# RX8Edaughter.net
KiCad netlist of a schematic drawn in EAGLE
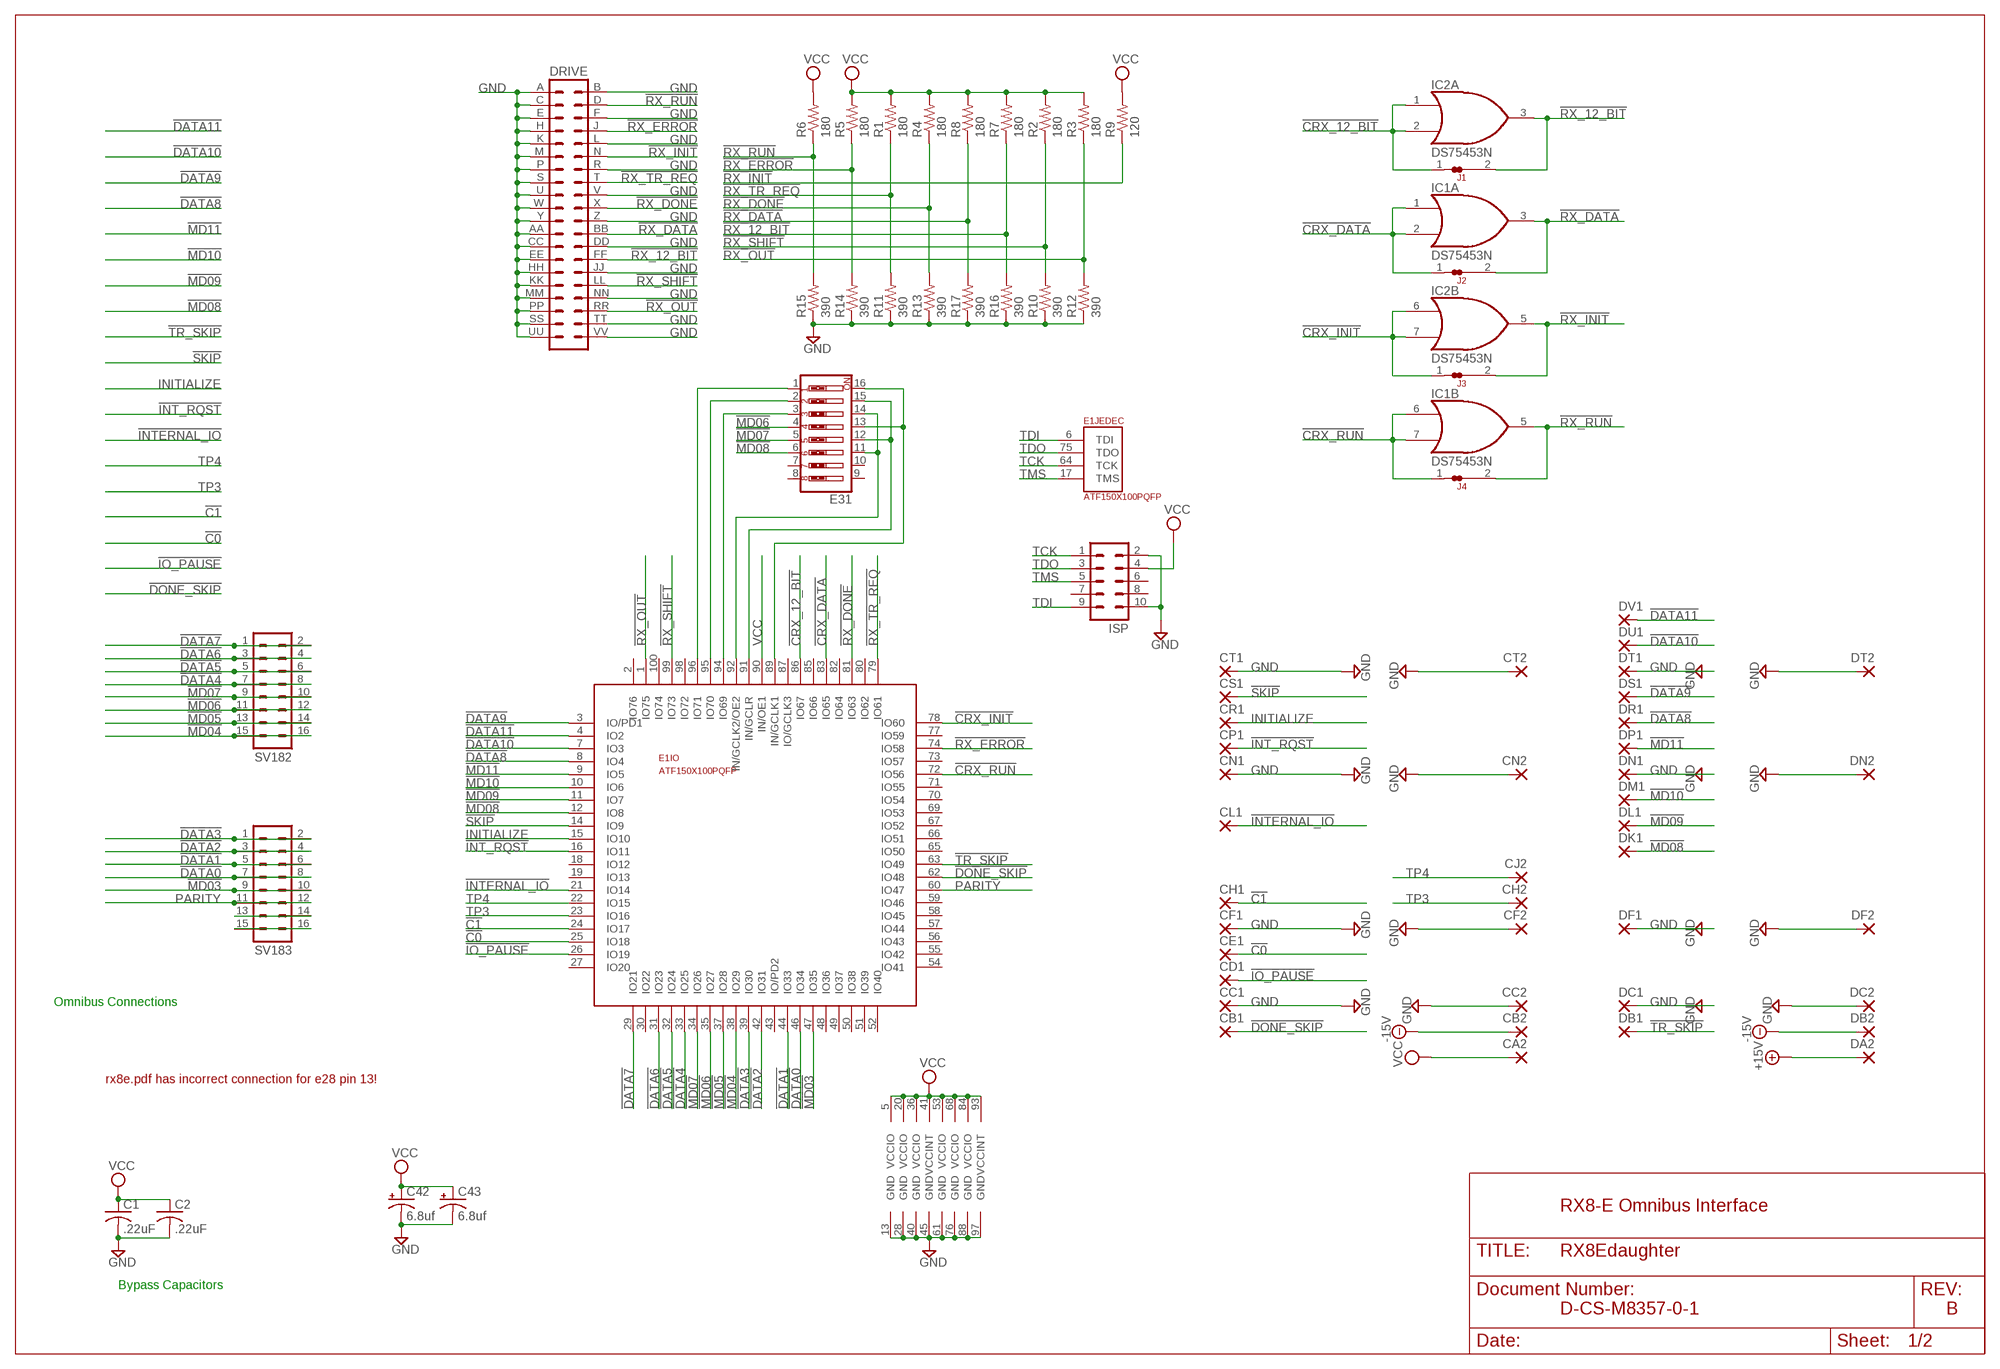
[diagram p0: schematic, sheet 1]
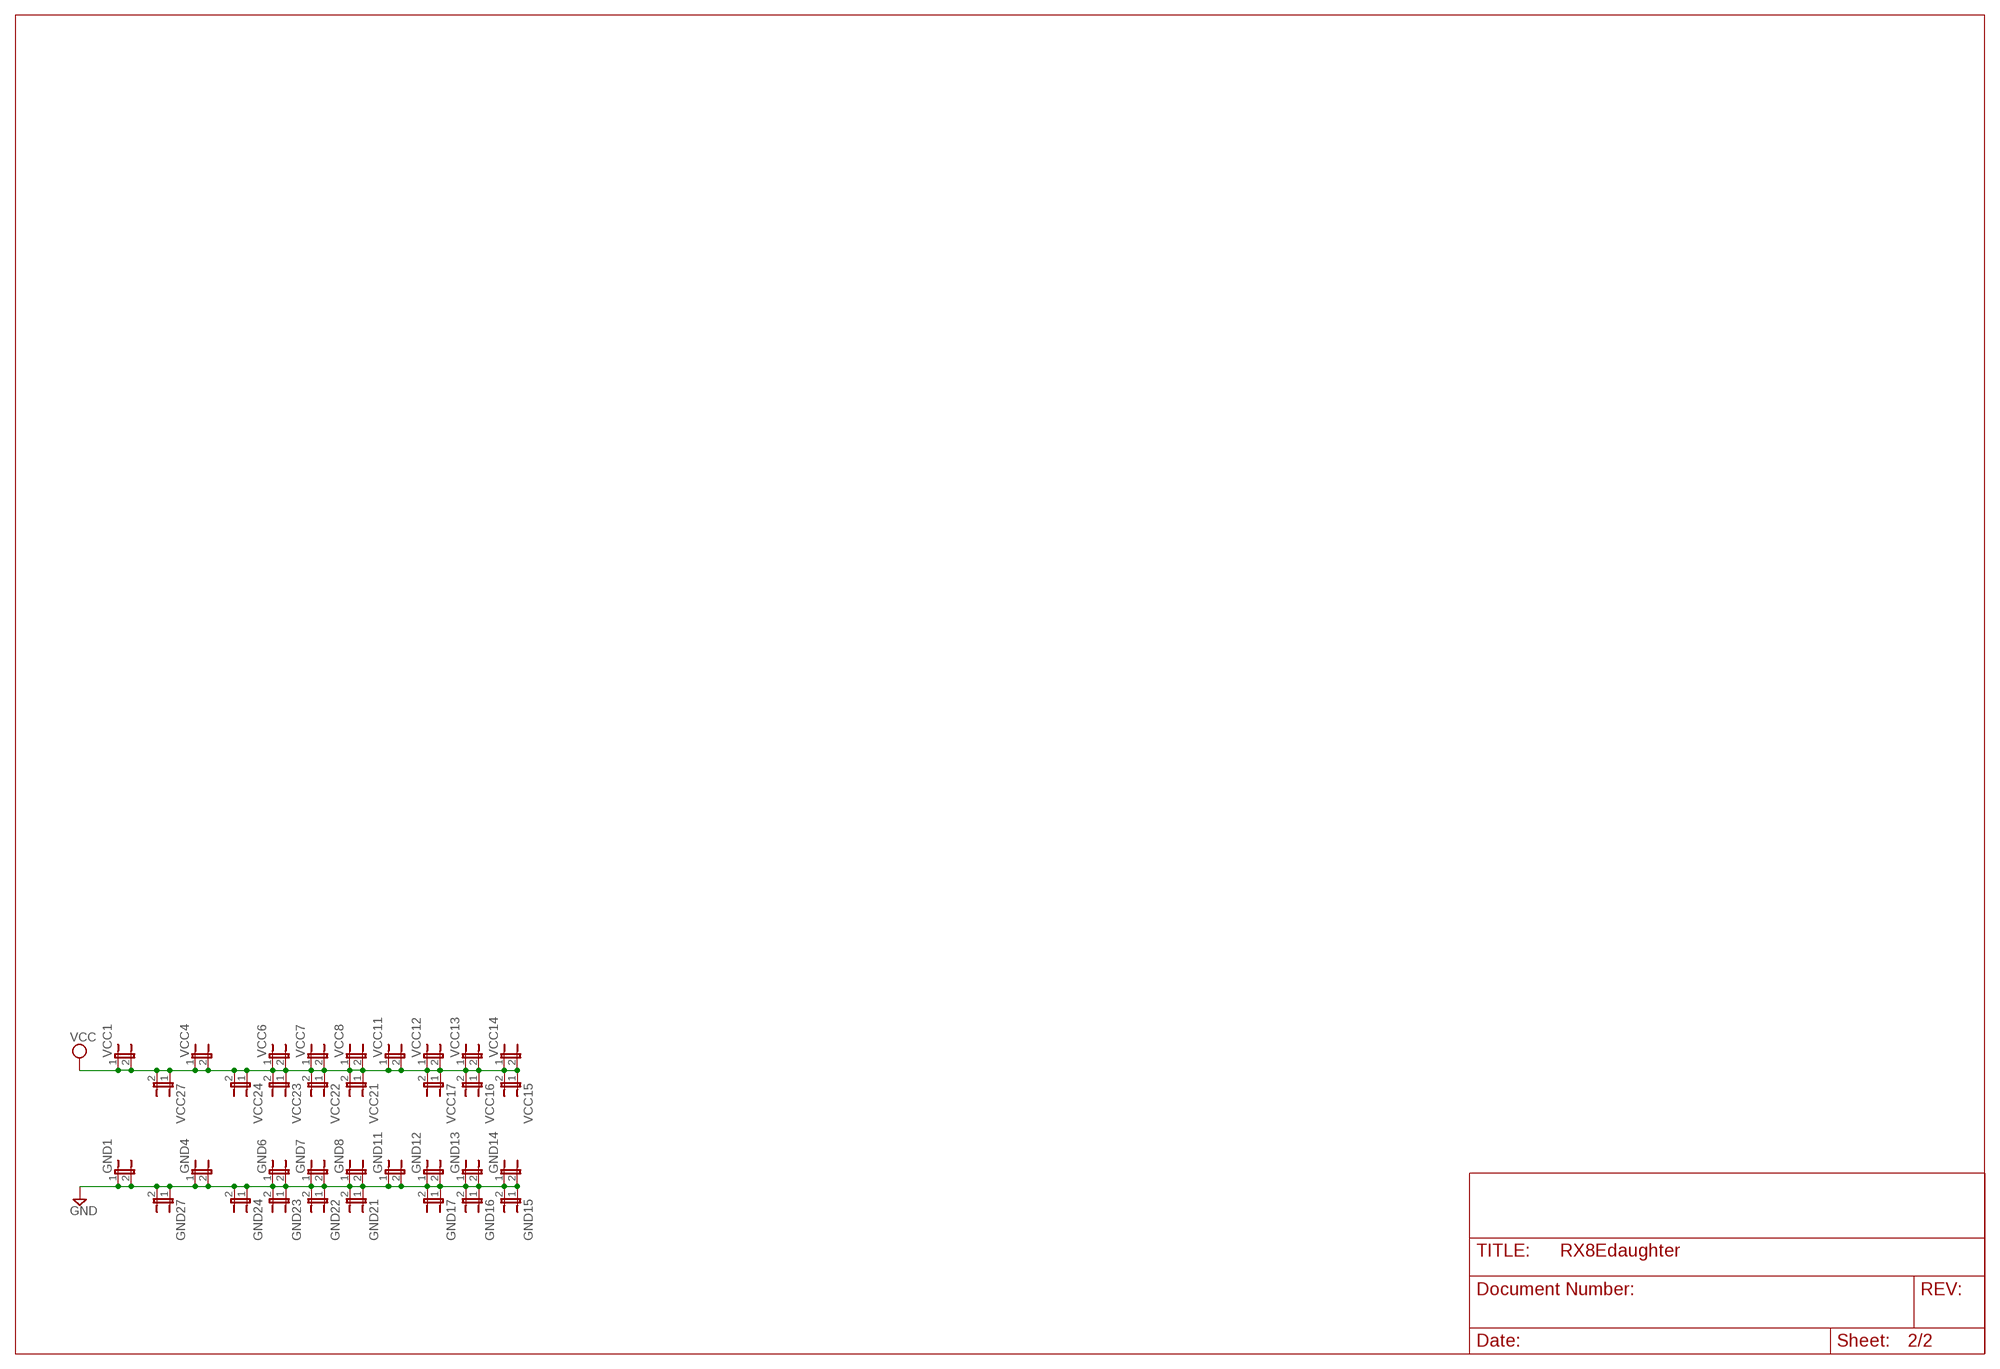
[diagram p1: schematic, sheet 2]

(export (version "E")
  (design (tool "Eeschema 10.0.6"))
  (components
    (comp (ref "GND1")
      (value "JP1E")
      (footprint "eagle-import:JP1")
      (libsource (lib "eagle-import") (part "JP1E"))
    )
    (comp (ref "GND4")
      (value "JP1E")
      (footprint "eagle-import:JP1")
      (libsource (lib "eagle-import") (part "JP1E"))
    )
    (comp (ref "GND6")
      (value "JP1E")
      (footprint "eagle-import:JP1")
      (libsource (lib "eagle-import") (part "JP1E"))
    )
    (comp (ref "GND7")
      (value "JP1E")
      (footprint "eagle-import:JP1")
      (libsource (lib "eagle-import") (part "JP1E"))
    )
    (comp (ref "GND8")
      (value "JP1E")
      (footprint "eagle-import:JP1")
      (libsource (lib "eagle-import") (part "JP1E"))
    )
    (comp (ref "GND11")
      (value "JP1E")
      (footprint "eagle-import:JP1")
      (libsource (lib "eagle-import") (part "JP1E"))
    )
    (comp (ref "GND12")
      (value "JP1E")
      (footprint "eagle-import:JP1")
      (libsource (lib "eagle-import") (part "JP1E"))
    )
    (comp (ref "GND13")
      (value "JP1E")
      (footprint "eagle-import:JP1")
      (libsource (lib "eagle-import") (part "JP1E"))
    )
    (comp (ref "GND14")
      (value "JP1E")
      (footprint "eagle-import:JP1")
      (libsource (lib "eagle-import") (part "JP1E"))
    )
    (comp (ref "GND15")
      (value "JP1E")
      (footprint "eagle-import:JP1")
      (libsource (lib "eagle-import") (part "JP1E"))
    )
    (comp (ref "GND16")
      (value "JP1E")
      (footprint "eagle-import:JP1")
      (libsource (lib "eagle-import") (part "JP1E"))
    )
    (comp (ref "GND17")
      (value "JP1E")
      (footprint "eagle-import:JP1")
      (libsource (lib "eagle-import") (part "JP1E"))
    )
    (comp (ref "GND21")
      (value "JP1E")
      (footprint "eagle-import:JP1")
      (libsource (lib "eagle-import") (part "JP1E"))
    )
    (comp (ref "GND22")
      (value "JP1E")
      (footprint "eagle-import:JP1")
      (libsource (lib "eagle-import") (part "JP1E"))
    )
    (comp (ref "GND23")
      (value "JP1E")
      (footprint "eagle-import:JP1")
      (libsource (lib "eagle-import") (part "JP1E"))
    )
    (comp (ref "GND24")
      (value "JP1E")
      (footprint "eagle-import:JP1")
      (libsource (lib "eagle-import") (part "JP1E"))
    )
    (comp (ref "GND27")
      (value "JP1E")
      (footprint "eagle-import:JP1")
      (libsource (lib "eagle-import") (part "JP1E"))
    )
    (comp (ref "VCC1")
      (value "JP1E")
      (footprint "eagle-import:JP1")
      (libsource (lib "eagle-import") (part "JP1E"))
    )
    (comp (ref "VCC4")
      (value "JP1E")
      (footprint "eagle-import:JP1")
      (libsource (lib "eagle-import") (part "JP1E"))
    )
    (comp (ref "VCC6")
      (value "JP1E")
      (footprint "eagle-import:JP1")
      (libsource (lib "eagle-import") (part "JP1E"))
    )
    (comp (ref "VCC7")
      (value "JP1E")
      (footprint "eagle-import:JP1")
      (libsource (lib "eagle-import") (part "JP1E"))
    )
    (comp (ref "VCC8")
      (value "JP1E")
      (footprint "eagle-import:JP1")
      (libsource (lib "eagle-import") (part "JP1E"))
    )
    (comp (ref "VCC11")
      (value "JP1E")
      (footprint "eagle-import:JP1")
      (libsource (lib "eagle-import") (part "JP1E"))
    )
    (comp (ref "VCC12")
      (value "JP1E")
      (footprint "eagle-import:JP1")
      (libsource (lib "eagle-import") (part "JP1E"))
    )
    (comp (ref "VCC13")
      (value "JP1E")
      (footprint "eagle-import:JP1")
      (libsource (lib "eagle-import") (part "JP1E"))
    )
    (comp (ref "VCC14")
      (value "JP1E")
      (footprint "eagle-import:JP1")
      (libsource (lib "eagle-import") (part "JP1E"))
    )
    (comp (ref "VCC15")
      (value "JP1E")
      (footprint "eagle-import:JP1")
      (libsource (lib "eagle-import") (part "JP1E"))
    )
    (comp (ref "VCC16")
      (value "JP1E")
      (footprint "eagle-import:JP1")
      (libsource (lib "eagle-import") (part "JP1E"))
    )
    (comp (ref "VCC17")
      (value "JP1E")
      (footprint "eagle-import:JP1")
      (libsource (lib "eagle-import") (part "JP1E"))
    )
    (comp (ref "VCC21")
      (value "JP1E")
      (footprint "eagle-import:JP1")
      (libsource (lib "eagle-import") (part "JP1E"))
    )
    (comp (ref "VCC22")
      (value "JP1E")
      (footprint "eagle-import:JP1")
      (libsource (lib "eagle-import") (part "JP1E"))
    )
    (comp (ref "VCC23")
      (value "JP1E")
      (footprint "eagle-import:JP1")
      (libsource (lib "eagle-import") (part "JP1E"))
    )
    (comp (ref "VCC24")
      (value "JP1E")
      (footprint "eagle-import:JP1")
      (libsource (lib "eagle-import") (part "JP1E"))
    )
    (comp (ref "VCC27")
      (value "JP1E")
      (footprint "eagle-import:JP1")
      (libsource (lib "eagle-import") (part "JP1E"))
    )
    (comp (ref "C1")
      (value ".22uF")
      (footprint "eagle-import:C050-025X075")
      (libsource (lib "eagle-import") (part "C-US050-025X075"))
    )
    (comp (ref "C2")
      (value ".22uF")
      (footprint "eagle-import:C050-025X075")
      (libsource (lib "eagle-import") (part "C-US050-025X075"))
    )
    (comp (ref "C42")
      (value "6.8uf")
      (footprint "eagle-import:E22-6")
      (libsource (lib "eagle-import") (part "CPOL-USE22-6AXIAL"))
    )
    (comp (ref "C43")
      (value "6.8uf")
      (footprint "eagle-import:E22-6")
      (libsource (lib "eagle-import") (part "CPOL-USE22-6AXIAL"))
    )
    (comp (ref "CA2")
      (value "1,6/0,9")
      (footprint "eagle-import:1,6_0,9")
      (libsource (lib "eagle-import") (part "1,6/0,9"))
    )
    (comp (ref "CB1")
      (value "1,6/0,9")
      (footprint "eagle-import:1,6_0,9")
      (libsource (lib "eagle-import") (part "1,6/0,9"))
    )
    (comp (ref "CB2")
      (value "1,6/0,9")
      (footprint "eagle-import:1,6_0,9")
      (libsource (lib "eagle-import") (part "1,6/0,9"))
    )
    (comp (ref "CC1")
      (value "1,6/0,9")
      (footprint "eagle-import:1,6_0,9")
      (libsource (lib "eagle-import") (part "1,6/0,9"))
    )
    (comp (ref "CC2")
      (value "1,6/0,9")
      (footprint "eagle-import:1,6_0,9")
      (libsource (lib "eagle-import") (part "1,6/0,9"))
    )
    (comp (ref "CD1")
      (value "1,6/0,9")
      (footprint "eagle-import:1,6_0,9")
      (libsource (lib "eagle-import") (part "1,6/0,9"))
    )
    (comp (ref "CE1")
      (value "1,6/0,9")
      (footprint "eagle-import:1,6_0,9")
      (libsource (lib "eagle-import") (part "1,6/0,9"))
    )
    (comp (ref "CF1")
      (value "1,6/0,9")
      (footprint "eagle-import:1,6_0,9")
      (libsource (lib "eagle-import") (part "1,6/0,9"))
    )
    (comp (ref "CF2")
      (value "1,6/0,9")
      (footprint "eagle-import:1,6_0,9")
      (libsource (lib "eagle-import") (part "1,6/0,9"))
    )
    (comp (ref "CH1")
      (value "1,6/0,9")
      (footprint "eagle-import:1,6_0,9")
      (libsource (lib "eagle-import") (part "1,6/0,9"))
    )
    (comp (ref "CH2")
      (value "1,6/0,9")
      (footprint "eagle-import:1,6_0,9")
      (libsource (lib "eagle-import") (part "1,6/0,9"))
    )
    (comp (ref "CJ2")
      (value "1,6/0,9")
      (footprint "eagle-import:1,6_0,9")
      (libsource (lib "eagle-import") (part "1,6/0,9"))
    )
    (comp (ref "CL1")
      (value "1,6/0,9")
      (footprint "eagle-import:1,6_0,9")
      (libsource (lib "eagle-import") (part "1,6/0,9"))
    )
    (comp (ref "CN1")
      (value "1,6/0,9")
      (footprint "eagle-import:1,6_0,9")
      (libsource (lib "eagle-import") (part "1,6/0,9"))
    )
    (comp (ref "CN2")
      (value "1,6/0,9")
      (footprint "eagle-import:1,6_0,9")
      (libsource (lib "eagle-import") (part "1,6/0,9"))
    )
    (comp (ref "CP1")
      (value "1,6/0,9")
      (footprint "eagle-import:1,6_0,9")
      (libsource (lib "eagle-import") (part "1,6/0,9"))
    )
    (comp (ref "CR1")
      (value "1,6/0,9")
      (footprint "eagle-import:1,6_0,9")
      (libsource (lib "eagle-import") (part "1,6/0,9"))
    )
    (comp (ref "CS1")
      (value "1,6/0,9")
      (footprint "eagle-import:1,6_0,9")
      (libsource (lib "eagle-import") (part "1,6/0,9"))
    )
    (comp (ref "CT1")
      (value "1,6/0,9")
      (footprint "eagle-import:1,6_0,9")
      (libsource (lib "eagle-import") (part "1,6/0,9"))
    )
    (comp (ref "CT2")
      (value "1,6/0,9")
      (footprint "eagle-import:1,6_0,9")
      (libsource (lib "eagle-import") (part "1,6/0,9"))
    )
    (comp (ref "DA2")
      (value "1,6/0,9")
      (footprint "eagle-import:1,6_0,9")
      (libsource (lib "eagle-import") (part "1,6/0,9"))
    )
    (comp (ref "DB1")
      (value "1,6/0,9")
      (footprint "eagle-import:1,6_0,9")
      (libsource (lib "eagle-import") (part "1,6/0,9"))
    )
    (comp (ref "DB2")
      (value "1,6/0,9")
      (footprint "eagle-import:1,6_0,9")
      (libsource (lib "eagle-import") (part "1,6/0,9"))
    )
    (comp (ref "DC1")
      (value "1,6/0,9")
      (footprint "eagle-import:1,6_0,9")
      (libsource (lib "eagle-import") (part "1,6/0,9"))
    )
    (comp (ref "DC2")
      (value "1,6/0,9")
      (footprint "eagle-import:1,6_0,9")
      (libsource (lib "eagle-import") (part "1,6/0,9"))
    )
    (comp (ref "DF1")
      (value "1,6/0,9")
      (footprint "eagle-import:1,6_0,9")
      (libsource (lib "eagle-import") (part "1,6/0,9"))
    )
    (comp (ref "DF2")
      (value "1,6/0,9")
      (footprint "eagle-import:1,6_0,9")
      (libsource (lib "eagle-import") (part "1,6/0,9"))
    )
    (comp (ref "DK1")
      (value "1,6/0,9")
      (footprint "eagle-import:1,6_0,9")
      (libsource (lib "eagle-import") (part "1,6/0,9"))
    )
    (comp (ref "DL1")
      (value "1,6/0,9")
      (footprint "eagle-import:1,6_0,9")
      (libsource (lib "eagle-import") (part "1,6/0,9"))
    )
    (comp (ref "DM1")
      (value "1,6/0,9")
      (footprint "eagle-import:1,6_0,9")
      (libsource (lib "eagle-import") (part "1,6/0,9"))
    )
    (comp (ref "DN1")
      (value "1,6/0,9")
      (footprint "eagle-import:1,6_0,9")
      (libsource (lib "eagle-import") (part "1,6/0,9"))
    )
    (comp (ref "DN2")
      (value "1,6/0,9")
      (footprint "eagle-import:1,6_0,9")
      (libsource (lib "eagle-import") (part "1,6/0,9"))
    )
    (comp (ref "DP1")
      (value "1,6/0,9")
      (footprint "eagle-import:1,6_0,9")
      (libsource (lib "eagle-import") (part "1,6/0,9"))
    )
    (comp (ref "DR1")
      (value "1,6/0,9")
      (footprint "eagle-import:1,6_0,9")
      (libsource (lib "eagle-import") (part "1,6/0,9"))
    )
    (comp (ref "DRIVE")
      (value "DEC40PINH")
      (footprint "eagle-import:DEC40PINH")
      (libsource (lib "eagle-import") (part "DEC40PINH"))
    )
    (comp (ref "DS1")
      (value "1,6/0,9")
      (footprint "eagle-import:1,6_0,9")
      (libsource (lib "eagle-import") (part "1,6/0,9"))
    )
    (comp (ref "DT1")
      (value "1,6/0,9")
      (footprint "eagle-import:1,6_0,9")
      (libsource (lib "eagle-import") (part "1,6/0,9"))
    )
    (comp (ref "DT2")
      (value "1,6/0,9")
      (footprint "eagle-import:1,6_0,9")
      (libsource (lib "eagle-import") (part "1,6/0,9"))
    )
    (comp (ref "DU1")
      (value "1,6/0,9")
      (footprint "eagle-import:1,6_0,9")
      (libsource (lib "eagle-import") (part "1,6/0,9"))
    )
    (comp (ref "DV1")
      (value "1,6/0,9")
      (footprint "eagle-import:1,6_0,9")
      (libsource (lib "eagle-import") (part "1,6/0,9"))
    )
    (comp (ref "E1")
      (value "ATF150X100PQFP")
      (footprint "eagle-import:PQFP-100")
      (libsource (lib "eagle-import") (part "ATF150X100PQFP"))
    )
    (comp (ref "E31")
      (value "SW_DIP-8")
      (footprint "eagle-import:EDG-08")
      (libsource (lib "eagle-import") (part "SW_DIP-8"))
    )
    (comp (ref "IC1")
      (value "DS75453N")
      (footprint "eagle-import:DIL08")
      (libsource (lib "eagle-import") (part "DS75453N"))
    )
    (comp (ref "IC2")
      (value "DS75453N")
      (footprint "eagle-import:DIL08")
      (libsource (lib "eagle-import") (part "DS75453N"))
    )
    (comp (ref "ISP")
      (value "ML10")
      (footprint "eagle-import:ML10")
      (libsource (lib "eagle-import") (part "ML10"))
    )
    (comp (ref "J1")
      (value "JUMPER-NC2")
      (footprint "eagle-import:NC2")
      (libsource (lib "eagle-import") (part "JUMPER-NC2"))
    )
    (comp (ref "J2")
      (value "JUMPER-NC2")
      (footprint "eagle-import:NC2")
      (libsource (lib "eagle-import") (part "JUMPER-NC2"))
    )
    (comp (ref "J3")
      (value "JUMPER-NC2")
      (footprint "eagle-import:NC2")
      (libsource (lib "eagle-import") (part "JUMPER-NC2"))
    )
    (comp (ref "J4")
      (value "JUMPER-NC2")
      (footprint "eagle-import:NC2")
      (libsource (lib "eagle-import") (part "JUMPER-NC2"))
    )
    (comp (ref "R1")
      (value "180")
      (footprint "eagle-import:0207_10")
      (libsource (lib "eagle-import") (part "R-US_0207/10"))
    )
    (comp (ref "R2")
      (value "180")
      (footprint "eagle-import:0207_10")
      (libsource (lib "eagle-import") (part "R-US_0207/10"))
    )
    (comp (ref "R3")
      (value "180")
      (footprint "eagle-import:0207_10")
      (libsource (lib "eagle-import") (part "R-US_0207/10"))
    )
    (comp (ref "R4")
      (value "180")
      (footprint "eagle-import:0207_10")
      (libsource (lib "eagle-import") (part "R-US_0207/10"))
    )
    (comp (ref "R5")
      (value "180")
      (footprint "eagle-import:0207_10")
      (libsource (lib "eagle-import") (part "R-US_0207/10"))
    )
    (comp (ref "R6")
      (value "180")
      (footprint "eagle-import:0207_10")
      (libsource (lib "eagle-import") (part "R-US_0207/10"))
    )
    (comp (ref "R7")
      (value "180")
      (footprint "eagle-import:0207_10")
      (libsource (lib "eagle-import") (part "R-US_0207/10"))
    )
    (comp (ref "R8")
      (value "180")
      (footprint "eagle-import:0207_10")
      (libsource (lib "eagle-import") (part "R-US_0207/10"))
    )
    (comp (ref "R9")
      (value "120")
      (footprint "eagle-import:0207_10")
      (libsource (lib "eagle-import") (part "R-US_0207/10"))
    )
    (comp (ref "R10")
      (value "390")
      (footprint "eagle-import:0207_10")
      (libsource (lib "eagle-import") (part "R-US_0207/10"))
    )
    (comp (ref "R11")
      (value "390")
      (footprint "eagle-import:0207_10")
      (libsource (lib "eagle-import") (part "R-US_0207/10"))
    )
    (comp (ref "R12")
      (value "390")
      (footprint "eagle-import:0207_10")
      (libsource (lib "eagle-import") (part "R-US_0207/10"))
    )
    (comp (ref "R13")
      (value "390")
      (footprint "eagle-import:0207_10")
      (libsource (lib "eagle-import") (part "R-US_0207/10"))
    )
    (comp (ref "R14")
      (value "390")
      (footprint "eagle-import:0207_10")
      (libsource (lib "eagle-import") (part "R-US_0207/10"))
    )
    (comp (ref "R15")
      (value "390")
      (footprint "eagle-import:0207_10")
      (libsource (lib "eagle-import") (part "R-US_0207/10"))
    )
    (comp (ref "R16")
      (value "390")
      (footprint "eagle-import:0207_10")
      (libsource (lib "eagle-import") (part "R-US_0207/10"))
    )
    (comp (ref "R17")
      (value "390")
      (footprint "eagle-import:0207_10")
      (libsource (lib "eagle-import") (part "R-US_0207/10"))
    )
    (comp (ref "SV182")
      (value "MA08-2")
      (footprint "eagle-import:MA08-2")
      (libsource (lib "eagle-import") (part "MA08-2"))
    )
    (comp (ref "SV183")
      (value "MA08-2")
      (footprint "eagle-import:MA08-2")
      (libsource (lib "eagle-import") (part "MA08-2"))
    )
  )
  (nets
    (net (code "1") (name "+15V") (class "Default")
      (node (ref "DA2") (pin "1") (pinfunction "P_1") (pintype "passive"))
    )
    (net (code "2") (name "-15V") (class "Default")
      (node (ref "CB2") (pin "1") (pinfunction "P_1") (pintype "passive"))
      (node (ref "DB2") (pin "1") (pinfunction "P_1") (pintype "passive"))
    )
    (net (code "3") (name "GND") (class "Default")
      (node (ref "C1") (pin "2") (pinfunction "2_2") (pintype "passive"))
      (node (ref "C2") (pin "2") (pinfunction "2_2") (pintype "passive"))
      (node (ref "C42") (pin "-") (pinfunction "-_-") (pintype "passive"))
      (node (ref "C43") (pin "-") (pinfunction "-_-") (pintype "passive"))
      (node (ref "CC1") (pin "1") (pinfunction "P_1") (pintype "passive"))
      (node (ref "CC2") (pin "1") (pinfunction "P_1") (pintype "passive"))
      (node (ref "CF1") (pin "1") (pinfunction "P_1") (pintype "passive"))
      (node (ref "CF2") (pin "1") (pinfunction "P_1") (pintype "passive"))
      (node (ref "CN1") (pin "1") (pinfunction "P_1") (pintype "passive"))
      (node (ref "CN2") (pin "1") (pinfunction "P_1") (pintype "passive"))
      (node (ref "CT1") (pin "1") (pinfunction "P_1") (pintype "passive"))
      (node (ref "CT2") (pin "1") (pinfunction "P_1") (pintype "passive"))
      (node (ref "DC1") (pin "1") (pinfunction "P_1") (pintype "passive"))
      (node (ref "DC2") (pin "1") (pinfunction "P_1") (pintype "passive"))
      (node (ref "DF1") (pin "1") (pinfunction "P_1") (pintype "passive"))
      (node (ref "DF2") (pin "1") (pinfunction "P_1") (pintype "passive"))
      (node (ref "DN1") (pin "1") (pinfunction "P_1") (pintype "passive"))
      (node (ref "DN2") (pin "1") (pinfunction "P_1") (pintype "passive"))
      (node (ref "DRIVE") (pin "A") (pinfunction "1_A") (pintype "bidirectional"))
      (node (ref "DRIVE") (pin "AA") (pinfunction "23_AA") (pintype "bidirectional"))
      (node (ref "DRIVE") (pin "B") (pinfunction "2_B") (pintype "bidirectional"))
      (node (ref "DRIVE") (pin "C") (pinfunction "3_C") (pintype "bidirectional"))
      (node (ref "DRIVE") (pin "CC") (pinfunction "25_CC") (pintype "bidirectional"))
      (node (ref "DRIVE") (pin "DD") (pinfunction "26_DD") (pintype "bidirectional"))
      (node (ref "DRIVE") (pin "E") (pinfunction "5_E") (pintype "bidirectional"))
      (node (ref "DRIVE") (pin "EE") (pinfunction "27_EE") (pintype "bidirectional"))
      (node (ref "DRIVE") (pin "F") (pinfunction "6_F") (pintype "bidirectional"))
      (node (ref "DRIVE") (pin "H") (pinfunction "7_H") (pintype "bidirectional"))
      (node (ref "DRIVE") (pin "HH") (pinfunction "29_HH") (pintype "bidirectional"))
      (node (ref "DRIVE") (pin "JJ") (pinfunction "30_JJ") (pintype "bidirectional"))
      (node (ref "DRIVE") (pin "K") (pinfunction "9_K") (pintype "bidirectional"))
      (node (ref "DRIVE") (pin "KK") (pinfunction "31_KK") (pintype "bidirectional"))
      (node (ref "DRIVE") (pin "L") (pinfunction "10_L") (pintype "bidirectional"))
      (node (ref "DRIVE") (pin "M") (pinfunction "11_M") (pintype "bidirectional"))
      (node (ref "DRIVE") (pin "MM") (pinfunction "33_MM") (pintype "bidirectional"))
      (node (ref "DRIVE") (pin "NN") (pinfunction "34_NN") (pintype "bidirectional"))
      (node (ref "DRIVE") (pin "P") (pinfunction "13_P") (pintype "bidirectional"))
      (node (ref "DRIVE") (pin "PP") (pinfunction "35_PP") (pintype "bidirectional"))
      (node (ref "DRIVE") (pin "R") (pinfunction "14_R") (pintype "bidirectional"))
      (node (ref "DRIVE") (pin "S") (pinfunction "15_S") (pintype "bidirectional"))
      (node (ref "DRIVE") (pin "SS") (pinfunction "37_SS") (pintype "bidirectional"))
      (node (ref "DRIVE") (pin "TT") (pinfunction "38_TT") (pintype "bidirectional"))
      (node (ref "DRIVE") (pin "U") (pinfunction "17_U") (pintype "bidirectional"))
      (node (ref "DRIVE") (pin "UU") (pinfunction "39_UU") (pintype "bidirectional"))
      (node (ref "DRIVE") (pin "V") (pinfunction "18_V") (pintype "bidirectional"))
      (node (ref "DRIVE") (pin "VV") (pinfunction "40_VV") (pintype "bidirectional"))
      (node (ref "DRIVE") (pin "W") (pinfunction "19_W") (pintype "bidirectional"))
      (node (ref "DRIVE") (pin "Y") (pinfunction "21_Y") (pintype "bidirectional"))
      (node (ref "DRIVE") (pin "Z") (pinfunction "22_Z") (pintype "bidirectional"))
      (node (ref "DT1") (pin "1") (pinfunction "P_1") (pintype "passive"))
      (node (ref "DT2") (pin "1") (pinfunction "P_1") (pintype "passive"))
      (node (ref "E1") (pin "13") (pinfunction "GND_13") (pintype "power_in"))
      (node (ref "E1") (pin "28") (pinfunction "GND_28") (pintype "power_in"))
      (node (ref "E1") (pin "40") (pinfunction "GND_40") (pintype "power_in"))
      (node (ref "E1") (pin "45") (pinfunction "GND_45") (pintype "power_in"))
      (node (ref "E1") (pin "61") (pinfunction "GND_61") (pintype "power_in"))
      (node (ref "E1") (pin "76") (pinfunction "GND_76") (pintype "power_in"))
      (node (ref "E1") (pin "88") (pinfunction "GND_88") (pintype "power_in"))
      (node (ref "E1") (pin "97") (pinfunction "GND_97") (pintype "power_in"))
      (node (ref "GND1") (pin "1") (pinfunction "1_1") (pintype "passive"))
      (node (ref "GND1") (pin "2") (pinfunction "2_2") (pintype "passive"))
      (node (ref "GND11") (pin "1") (pinfunction "1_1") (pintype "passive"))
      (node (ref "GND11") (pin "2") (pinfunction "2_2") (pintype "passive"))
      (node (ref "GND12") (pin "1") (pinfunction "1_1") (pintype "passive"))
      (node (ref "GND12") (pin "2") (pinfunction "2_2") (pintype "passive"))
      (node (ref "GND13") (pin "1") (pinfunction "1_1") (pintype "passive"))
      (node (ref "GND13") (pin "2") (pinfunction "2_2") (pintype "passive"))
      (node (ref "GND14") (pin "1") (pinfunction "1_1") (pintype "passive"))
      (node (ref "GND14") (pin "2") (pinfunction "2_2") (pintype "passive"))
      (node (ref "GND15") (pin "1") (pinfunction "1_1") (pintype "passive"))
      (node (ref "GND15") (pin "2") (pinfunction "2_2") (pintype "passive"))
      (node (ref "GND16") (pin "1") (pinfunction "1_1") (pintype "passive"))
      (node (ref "GND16") (pin "2") (pinfunction "2_2") (pintype "passive"))
      (node (ref "GND17") (pin "1") (pinfunction "1_1") (pintype "passive"))
      (node (ref "GND17") (pin "2") (pinfunction "2_2") (pintype "passive"))
      (node (ref "GND21") (pin "1") (pinfunction "1_1") (pintype "passive"))
      (node (ref "GND21") (pin "2") (pinfunction "2_2") (pintype "passive"))
      (node (ref "GND22") (pin "1") (pinfunction "1_1") (pintype "passive"))
      (node (ref "GND22") (pin "2") (pinfunction "2_2") (pintype "passive"))
      (node (ref "GND23") (pin "1") (pinfunction "1_1") (pintype "passive"))
      (node (ref "GND23") (pin "2") (pinfunction "2_2") (pintype "passive"))
      (node (ref "GND24") (pin "1") (pinfunction "1_1") (pintype "passive"))
      (node (ref "GND24") (pin "2") (pinfunction "2_2") (pintype "passive"))
      (node (ref "GND27") (pin "1") (pinfunction "1_1") (pintype "passive"))
      (node (ref "GND27") (pin "2") (pinfunction "2_2") (pintype "passive"))
      (node (ref "GND4") (pin "1") (pinfunction "1_1") (pintype "passive"))
      (node (ref "GND4") (pin "2") (pinfunction "2_2") (pintype "passive"))
      (node (ref "GND6") (pin "1") (pinfunction "1_1") (pintype "passive"))
      (node (ref "GND6") (pin "2") (pinfunction "2_2") (pintype "passive"))
      (node (ref "GND7") (pin "1") (pinfunction "1_1") (pintype "passive"))
      (node (ref "GND7") (pin "2") (pinfunction "2_2") (pintype "passive"))
      (node (ref "GND8") (pin "1") (pinfunction "1_1") (pintype "passive"))
      (node (ref "GND8") (pin "2") (pinfunction "2_2") (pintype "passive"))
      (node (ref "ISP") (pin "10") (pinfunction "10_10") (pintype "passive"))
      (node (ref "ISP") (pin "2") (pinfunction "2_2") (pintype "passive"))
      (node (ref "R10") (pin "1") (pinfunction "1_1") (pintype "passive"))
      (node (ref "R11") (pin "1") (pinfunction "1_1") (pintype "passive"))
      (node (ref "R12") (pin "1") (pinfunction "1_1") (pintype "passive"))
      (node (ref "R13") (pin "1") (pinfunction "1_1") (pintype "passive"))
      (node (ref "R14") (pin "1") (pinfunction "1_1") (pintype "passive"))
      (node (ref "R15") (pin "1") (pinfunction "1_1") (pintype "passive"))
      (node (ref "R16") (pin "1") (pinfunction "1_1") (pintype "passive"))
      (node (ref "R17") (pin "1") (pinfunction "1_1") (pintype "passive"))
    )
    (net (code "4") (name "INITIALIZE") (class "Default")
      (node (ref "CR1") (pin "1") (pinfunction "P_1") (pintype "passive"))
      (node (ref "E1") (pin "15") (pinfunction "IO10_15") (pintype "bidirectional"))
    )
    (net (code "5") (name "Net-(E1Q-IN{slash}GCLK1)") (class "Default")
      (node (ref "E1") (pin "89") (pinfunction "IN/GCLK1_89") (pintype "input"))
      (node (ref "E31") (pin "13") (pinfunction "13_13") (pintype "passive"))
      (node (ref "E31") (pin "16") (pinfunction "16_16") (pintype "passive"))
    )
    (net (code "6") (name "Net-(E1Q-IN{slash}GCLK2{slash}OE2)") (class "Default")
      (node (ref "E1") (pin "92") (pinfunction "IN/GCLK2/OE2_92") (pintype "input"))
      (node (ref "E31") (pin "11") (pinfunction "11_11") (pintype "passive"))
      (node (ref "E31") (pin "14") (pinfunction "14_14") (pintype "passive"))
    )
    (net (code "7") (name "Net-(E1Q-IN{slash}GCLR)") (class "Default")
      (node (ref "E1") (pin "91") (pinfunction "IN/GCLR_91") (pintype "input"))
      (node (ref "E31") (pin "12") (pinfunction "12_12") (pintype "passive"))
      (node (ref "E31") (pin "15") (pinfunction "15_15") (pintype "passive"))
    )
    (net (code "8") (name "Net-(E1Q-IO69)") (class "Default")
      (node (ref "E1") (pin "94") (pinfunction "IO69_94") (pintype "bidirectional"))
      (node (ref "E31") (pin "3") (pinfunction "3_3") (pintype "passive"))
    )
    (net (code "9") (name "Net-(E1Q-IO70)") (class "Default")
      (node (ref "E1") (pin "95") (pinfunction "IO70_95") (pintype "bidirectional"))
      (node (ref "E31") (pin "2") (pinfunction "2_2") (pintype "passive"))
    )
    (net (code "10") (name "Net-(E1Q-IO71)") (class "Default")
      (node (ref "E1") (pin "96") (pinfunction "IO71_96") (pintype "bidirectional"))
      (node (ref "E31") (pin "1") (pinfunction "1_1") (pintype "passive"))
    )
    (net (code "11") (name "Net-(SV183-Pad13)") (class "Default")
      (node (ref "SV183") (pin "13") (pinfunction "13_13") (pintype "passive"))
      (node (ref "SV183") (pin "14") (pinfunction "14_14") (pintype "passive"))
    )
    (net (code "12") (name "Net-(SV183-Pad15)") (class "Default")
      (node (ref "SV183") (pin "15") (pinfunction "15_15") (pintype "passive"))
      (node (ref "SV183") (pin "16") (pinfunction "16_16") (pintype "passive"))
    )
    (net (code "13") (name "PARITY") (class "Default")
      (node (ref "E1") (pin "60") (pinfunction "IO47_60") (pintype "bidirectional"))
      (node (ref "SV183") (pin "11") (pinfunction "11_11") (pintype "passive"))
      (node (ref "SV183") (pin "12") (pinfunction "12_12") (pintype "passive"))
    )
    (net (code "14") (name "TCK") (class "Default")
      (node (ref "E1") (pin "64") (pinfunction "TCK_64") (pintype "bidirectional"))
      (node (ref "ISP") (pin "1") (pinfunction "1_1") (pintype "passive"))
    )
    (net (code "15") (name "TDI") (class "Default")
      (node (ref "E1") (pin "6") (pinfunction "TDI_6") (pintype "bidirectional"))
      (node (ref "ISP") (pin "9") (pinfunction "9_9") (pintype "passive"))
    )
    (net (code "16") (name "TDO") (class "Default")
      (node (ref "E1") (pin "75") (pinfunction "TDO_75") (pintype "bidirectional"))
      (node (ref "ISP") (pin "3") (pinfunction "3_3") (pintype "passive"))
    )
    (net (code "17") (name "TMS") (class "Default")
      (node (ref "E1") (pin "17") (pinfunction "TMS_17") (pintype "bidirectional"))
      (node (ref "ISP") (pin "5") (pinfunction "5_5") (pintype "passive"))
    )
    (net (code "18") (name "TP3") (class "Default")
      (node (ref "CH2") (pin "1") (pinfunction "P_1") (pintype "passive"))
      (node (ref "E1") (pin "23") (pinfunction "IO16_23") (pintype "bidirectional"))
    )
    (net (code "19") (name "TP4") (class "Default")
      (node (ref "CJ2") (pin "1") (pinfunction "P_1") (pintype "passive"))
      (node (ref "E1") (pin "22") (pinfunction "IO15_22") (pintype "bidirectional"))
    )
    (net (code "20") (name "VCC") (class "Default")
      (node (ref "C1") (pin "1") (pinfunction "1_1") (pintype "passive"))
      (node (ref "C2") (pin "1") (pinfunction "1_1") (pintype "passive"))
      (node (ref "C42") (pin "+") (pinfunction "+_+") (pintype "passive"))
      (node (ref "C43") (pin "+") (pinfunction "+_+") (pintype "passive"))
      (node (ref "CA2") (pin "1") (pinfunction "P_1") (pintype "passive"))
      (node (ref "E1") (pin "20") (pinfunction "VCCIO_20") (pintype "power_in"))
      (node (ref "E1") (pin "36") (pinfunction "VCCIO_36") (pintype "power_in"))
      (node (ref "E1") (pin "41") (pinfunction "VCCINT_41") (pintype "power_in"))
      (node (ref "E1") (pin "5") (pinfunction "VCCIO_5") (pintype "power_in"))
      (node (ref "E1") (pin "53") (pinfunction "VCCIO_53") (pintype "power_in"))
      (node (ref "E1") (pin "68") (pinfunction "VCCIO_68") (pintype "power_in"))
      (node (ref "E1") (pin "84") (pinfunction "VCCIO_84") (pintype "power_in"))
      (node (ref "E1") (pin "90") (pinfunction "IN/OE1_90") (pintype "input"))
      (node (ref "E1") (pin "93") (pinfunction "VCCINT_93") (pintype "power_in"))
      (node (ref "ISP") (pin "4") (pinfunction "4_4") (pintype "passive"))
      (node (ref "R1") (pin "2") (pinfunction "2_2") (pintype "passive"))
      (node (ref "R2") (pin "2") (pinfunction "2_2") (pintype "passive"))
      (node (ref "R3") (pin "2") (pinfunction "2_2") (pintype "passive"))
      (node (ref "R4") (pin "2") (pinfunction "2_2") (pintype "passive"))
      (node (ref "R5") (pin "2") (pinfunction "2_2") (pintype "passive"))
      (node (ref "R6") (pin "2") (pinfunction "2_2") (pintype "passive"))
      (node (ref "R7") (pin "2") (pinfunction "2_2") (pintype "passive"))
      (node (ref "R8") (pin "2") (pinfunction "2_2") (pintype "passive"))
      (node (ref "R9") (pin "2") (pinfunction "2_2") (pintype "passive"))
      (node (ref "VCC1") (pin "1") (pinfunction "1_1") (pintype "passive"))
      (node (ref "VCC1") (pin "2") (pinfunction "2_2") (pintype "passive"))
      (node (ref "VCC11") (pin "1") (pinfunction "1_1") (pintype "passive"))
      (node (ref "VCC11") (pin "2") (pinfunction "2_2") (pintype "passive"))
      (node (ref "VCC12") (pin "1") (pinfunction "1_1") (pintype "passive"))
      (node (ref "VCC12") (pin "2") (pinfunction "2_2") (pintype "passive"))
      (node (ref "VCC13") (pin "1") (pinfunction "1_1") (pintype "passive"))
      (node (ref "VCC13") (pin "2") (pinfunction "2_2") (pintype "passive"))
      (node (ref "VCC14") (pin "1") (pinfunction "1_1") (pintype "passive"))
      (node (ref "VCC14") (pin "2") (pinfunction "2_2") (pintype "passive"))
      (node (ref "VCC15") (pin "1") (pinfunction "1_1") (pintype "passive"))
      (node (ref "VCC15") (pin "2") (pinfunction "2_2") (pintype "passive"))
      (node (ref "VCC16") (pin "1") (pinfunction "1_1") (pintype "passive"))
      (node (ref "VCC16") (pin "2") (pinfunction "2_2") (pintype "passive"))
      (node (ref "VCC17") (pin "1") (pinfunction "1_1") (pintype "passive"))
      (node (ref "VCC17") (pin "2") (pinfunction "2_2") (pintype "passive"))
      (node (ref "VCC21") (pin "1") (pinfunction "1_1") (pintype "passive"))
      (node (ref "VCC21") (pin "2") (pinfunction "2_2") (pintype "passive"))
      (node (ref "VCC22") (pin "1") (pinfunction "1_1") (pintype "passive"))
      (node (ref "VCC22") (pin "2") (pinfunction "2_2") (pintype "passive"))
      (node (ref "VCC23") (pin "1") (pinfunction "1_1") (pintype "passive"))
      (node (ref "VCC23") (pin "2") (pinfunction "2_2") (pintype "passive"))
      (node (ref "VCC24") (pin "1") (pinfunction "1_1") (pintype "passive"))
      (node (ref "VCC24") (pin "2") (pinfunction "2_2") (pintype "passive"))
      (node (ref "VCC27") (pin "1") (pinfunction "1_1") (pintype "passive"))
      (node (ref "VCC27") (pin "2") (pinfunction "2_2") (pintype "passive"))
      (node (ref "VCC4") (pin "1") (pinfunction "1_1") (pintype "passive"))
      (node (ref "VCC4") (pin "2") (pinfunction "2_2") (pintype "passive"))
      (node (ref "VCC6") (pin "1") (pinfunction "1_1") (pintype "passive"))
      (node (ref "VCC6") (pin "2") (pinfunction "2_2") (pintype "passive"))
      (node (ref "VCC7") (pin "1") (pinfunction "1_1") (pintype "passive"))
      (node (ref "VCC7") (pin "2") (pinfunction "2_2") (pintype "passive"))
      (node (ref "VCC8") (pin "1") (pinfunction "1_1") (pintype "passive"))
      (node (ref "VCC8") (pin "2") (pinfunction "2_2") (pintype "passive"))
    )
    (net (code "21") (name "unconnected-(E1Q-IO12-Pad18)") (class "Default")
      (node (ref "E1") (pin "18") (pinfunction "IO12_18") (pintype "bidirectional"))
    )
    (net (code "22") (name "unconnected-(E1Q-IO13-Pad19)") (class "Default")
      (node (ref "E1") (pin "19") (pinfunction "IO13_19") (pintype "bidirectional"))
    )
    (net (code "23") (name "unconnected-(E1Q-IO20-Pad27)") (class "Default")
      (node (ref "E1") (pin "27") (pinfunction "IO20_27") (pintype "bidirectional"))
    )
    (net (code "24") (name "unconnected-(E1Q-IO22-Pad30)") (class "Default")
      (node (ref "E1") (pin "30") (pinfunction "IO22_30") (pintype "bidirectional"))
    )
    (net (code "25") (name "unconnected-(E1Q-IO36-Pad48)") (class "Default")
      (node (ref "E1") (pin "48") (pinfunction "IO36_48") (pintype "bidirectional"))
    )
    (net (code "26") (name "unconnected-(E1Q-IO37-Pad49)") (class "Default")
      (node (ref "E1") (pin "49") (pinfunction "IO37_49") (pintype "bidirectional"))
    )
    (net (code "27") (name "unconnected-(E1Q-IO38-Pad50)") (class "Default")
      (node (ref "E1") (pin "50") (pinfunction "IO38_50") (pintype "bidirectional"))
    )
    (net (code "28") (name "unconnected-(E1Q-IO39-Pad51)") (class "Default")
      (node (ref "E1") (pin "51") (pinfunction "IO39_51") (pintype "bidirectional"))
    )
    (net (code "29") (name "unconnected-(E1Q-IO40-Pad52)") (class "Default")
      (node (ref "E1") (pin "52") (pinfunction "IO40_52") (pintype "bidirectional"))
    )
    (net (code "30") (name "unconnected-(E1Q-IO41-Pad54)") (class "Default")
      (node (ref "E1") (pin "54") (pinfunction "IO41_54") (pintype "bidirectional"))
    )
    (net (code "31") (name "unconnected-(E1Q-IO42-Pad55)") (class "Default")
      (node (ref "E1") (pin "55") (pinfunction "IO42_55") (pintype "bidirectional"))
    )
    (net (code "32") (name "unconnected-(E1Q-IO43-Pad56)") (class "Default")
      (node (ref "E1") (pin "56") (pinfunction "IO43_56") (pintype "bidirectional"))
    )
    (net (code "33") (name "unconnected-(E1Q-IO44-Pad57)") (class "Default")
      (node (ref "E1") (pin "57") (pinfunction "IO44_57") (pintype "bidirectional"))
    )
    (net (code "34") (name "unconnected-(E1Q-IO45-Pad58)") (class "Default")
      (node (ref "E1") (pin "58") (pinfunction "IO45_58") (pintype "bidirectional"))
    )
    (net (code "35") (name "unconnected-(E1Q-IO46-Pad59)") (class "Default")
      (node (ref "E1") (pin "59") (pinfunction "IO46_59") (pintype "bidirectional"))
    )
    (net (code "36") (name "unconnected-(E1Q-IO50-Pad65)") (class "Default")
      (node (ref "E1") (pin "65") (pinfunction "IO50_65") (pintype "bidirectional"))
    )
    (net (code "37") (name "unconnected-(E1Q-IO51-Pad66)") (class "Default")
      (node (ref "E1") (pin "66") (pinfunction "IO51_66") (pintype "bidirectional"))
    )
    (net (code "38") (name "unconnected-(E1Q-IO52-Pad67)") (class "Default")
      (node (ref "E1") (pin "67") (pinfunction "IO52_67") (pintype "bidirectional"))
    )
    (net (code "39") (name "unconnected-(E1Q-IO53-Pad69)") (class "Default")
      (node (ref "E1") (pin "69") (pinfunction "IO53_69") (pintype "bidirectional"))
    )
    (net (code "40") (name "unconnected-(E1Q-IO54-Pad70)") (class "Default")
      (node (ref "E1") (pin "70") (pinfunction "IO54_70") (pintype "bidirectional"))
    )
    (net (code "41") (name "unconnected-(E1Q-IO55-Pad71)") (class "Default")
      (node (ref "E1") (pin "71") (pinfunction "IO55_71") (pintype "bidirectional"))
    )
    (net (code "42") (name "unconnected-(E1Q-IO57-Pad73)") (class "Default")
      (node (ref "E1") (pin "73") (pinfunction "IO57_73") (pintype "bidirectional"))
    )
    (net (code "43") (name "unconnected-(E1Q-IO59-Pad77)") (class "Default")
      (node (ref "E1") (pin "77") (pinfunction "IO59_77") (pintype "bidirectional"))
    )
    (net (code "44") (name "unconnected-(E1Q-IO62-Pad80)") (class "Default")
      (node (ref "E1") (pin "80") (pinfunction "IO62_80") (pintype "bidirectional"))
    )
    (net (code "45") (name "unconnected-(E1Q-IO64-Pad82)") (class "Default")
      (node (ref "E1") (pin "82") (pinfunction "IO64_82") (pintype "bidirectional"))
    )
    (net (code "46") (name "unconnected-(E1Q-IO66-Pad85)") (class "Default")
      (node (ref "E1") (pin "85") (pinfunction "IO66_85") (pintype "bidirectional"))
    )
    (net (code "47") (name "unconnected-(E1Q-IO72-Pad98)") (class "Default")
      (node (ref "E1") (pin "98") (pinfunction "IO72_98") (pintype "bidirectional"))
    )
    (net (code "48") (name "unconnected-(E1Q-IO74-Pad100)") (class "Default")
      (node (ref "E1") (pin "100") (pinfunction "IO74_100") (pintype "bidirectional"))
    )
    (net (code "49") (name "unconnected-(E1Q-IO76-Pad2)") (class "Default")
      (node (ref "E1") (pin "2") (pinfunction "IO76_2") (pintype "bidirectional"))
    )
    (net (code "50") (name "unconnected-(E1Q-IO{slash}GCLK3-Pad87)") (class "Default")
      (node (ref "E1") (pin "87") (pinfunction "IO/GCLK3_87") (pintype "bidirectional"))
    )
    (net (code "51") (name "unconnected-(E1Q-IO{slash}PD2-Pad43)") (class "Default")
      (node (ref "E1") (pin "43") (pinfunction "IO/PD2_43") (pintype "bidirectional"))
    )
    (net (code "52") (name "unconnected-(E31-Pad7)") (class "Default")
      (node (ref "E31") (pin "7") (pinfunction "7_7") (pintype "passive"))
    )
    (net (code "53") (name "unconnected-(E31-Pad8)") (class "Default")
      (node (ref "E31") (pin "8") (pinfunction "8_8") (pintype "passive"))
    )
    (net (code "54") (name "unconnected-(E31-Pad9)") (class "Default")
      (node (ref "E31") (pin "9") (pinfunction "9_9") (pintype "passive"))
    )
    (net (code "55") (name "unconnected-(E31-Pad10)") (class "Default")
      (node (ref "E31") (pin "10") (pinfunction "10_10") (pintype "passive"))
    )
    (net (code "56") (name "unconnected-(ISP-Pad6)") (class "Default")
      (node (ref "ISP") (pin "6") (pinfunction "6_6") (pintype "passive"))
    )
    (net (code "57") (name "unconnected-(ISP-Pad7)") (class "Default")
      (node (ref "ISP") (pin "7") (pinfunction "7_7") (pintype "passive"))
    )
    (net (code "58") (name "unconnected-(ISP-Pad8)") (class "Default")
      (node (ref "ISP") (pin "8") (pinfunction "8_8") (pintype "passive"))
    )
    (net (code "59") (name "~{C0}") (class "Default")
      (node (ref "CE1") (pin "1") (pinfunction "P_1") (pintype "passive"))
      (node (ref "E1") (pin "25") (pinfunction "IO18_25") (pintype "bidirectional"))
    )
    (net (code "60") (name "~{C1}") (class "Default")
      (node (ref "CH1") (pin "1") (pinfunction "P_1") (pintype "passive"))
      (node (ref "E1") (pin "24") (pinfunction "IO17_24") (pintype "bidirectional"))
    )
    (net (code "61") (name "~{CRX_12_BIT}") (class "Default")
      (node (ref "E1") (pin "86") (pinfunction "IO67_86") (pintype "bidirectional"))
      (node (ref "IC2") (pin "1") (pinfunction "I0_1") (pintype "input"))
      (node (ref "IC2") (pin "2") (pinfunction "I1_2") (pintype "input"))
      (node (ref "J1") (pin "1") (pinfunction "1_1") (pintype "bidirectional"))
    )
    (net (code "62") (name "~{CRX_DATA}") (class "Default")
      (node (ref "E1") (pin "83") (pinfunction "IO65_83") (pintype "bidirectional"))
      (node (ref "IC1") (pin "1") (pinfunction "I0_1") (pintype "input"))
      (node (ref "IC1") (pin "2") (pinfunction "I1_2") (pintype "input"))
      (node (ref "J2") (pin "1") (pinfunction "1_1") (pintype "bidirectional"))
    )
    (net (code "63") (name "~{CRX_INIT}") (class "Default")
      (node (ref "E1") (pin "78") (pinfunction "IO60_78") (pintype "bidirectional"))
      (node (ref "IC2") (pin "6") (pinfunction "I0_6") (pintype "input"))
      (node (ref "IC2") (pin "7") (pinfunction "I1_7") (pintype "input"))
      (node (ref "J3") (pin "1") (pinfunction "1_1") (pintype "bidirectional"))
    )
    (net (code "64") (name "~{CRX_RUN}") (class "Default")
      (node (ref "E1") (pin "72") (pinfunction "IO56_72") (pintype "bidirectional"))
      (node (ref "IC1") (pin "6") (pinfunction "I0_6") (pintype "input"))
      (node (ref "IC1") (pin "7") (pinfunction "I1_7") (pintype "input"))
      (node (ref "J4") (pin "1") (pinfunction "1_1") (pintype "bidirectional"))
    )
    (net (code "65") (name "~{DATA0}") (class "Default")
      (node (ref "E1") (pin "46") (pinfunction "IO34_46") (pintype "bidirectional"))
      (node (ref "SV183") (pin "7") (pinfunction "7_7") (pintype "passive"))
      (node (ref "SV183") (pin "8") (pinfunction "8_8") (pintype "passive"))
    )
    (net (code "66") (name "~{DATA1}") (class "Default")
      (node (ref "E1") (pin "44") (pinfunction "IO33_44") (pintype "bidirectional"))
      (node (ref "SV183") (pin "5") (pinfunction "5_5") (pintype "passive"))
      (node (ref "SV183") (pin "6") (pinfunction "6_6") (pintype "passive"))
    )
    (net (code "67") (name "~{DATA2}") (class "Default")
      (node (ref "E1") (pin "42") (pinfunction "IO31_42") (pintype "bidirectional"))
      (node (ref "SV183") (pin "3") (pinfunction "3_3") (pintype "passive"))
      (node (ref "SV183") (pin "4") (pinfunction "4_4") (pintype "passive"))
    )
    (net (code "68") (name "~{DATA3}") (class "Default")
      (node (ref "E1") (pin "39") (pinfunction "IO30_39") (pintype "bidirectional"))
      (node (ref "SV183") (pin "1") (pinfunction "1_1") (pintype "passive"))
      (node (ref "SV183") (pin "2") (pinfunction "2_2") (pintype "passive"))
    )
    (net (code "69") (name "~{DATA4}") (class "Default")
      (node (ref "E1") (pin "33") (pinfunction "IO25_33") (pintype "bidirectional"))
      (node (ref "SV182") (pin "7") (pinfunction "7_7") (pintype "passive"))
      (node (ref "SV182") (pin "8") (pinfunction "8_8") (pintype "passive"))
    )
    (net (code "70") (name "~{DATA5}") (class "Default")
      (node (ref "E1") (pin "32") (pinfunction "IO24_32") (pintype "bidirectional"))
      (node (ref "SV182") (pin "5") (pinfunction "5_5") (pintype "passive"))
      (node (ref "SV182") (pin "6") (pinfunction "6_6") (pintype "passive"))
    )
    (net (code "71") (name "~{DATA6}") (class "Default")
      (node (ref "E1") (pin "31") (pinfunction "IO23_31") (pintype "bidirectional"))
      (node (ref "SV182") (pin "3") (pinfunction "3_3") (pintype "passive"))
      (node (ref "SV182") (pin "4") (pinfunction "4_4") (pintype "passive"))
    )
    (net (code "72") (name "~{DATA7}") (class "Default")
      (node (ref "E1") (pin "29") (pinfunction "IO21_29") (pintype "bidirectional"))
      (node (ref "SV182") (pin "1") (pinfunction "1_1") (pintype "passive"))
      (node (ref "SV182") (pin "2") (pinfunction "2_2") (pintype "passive"))
    )
    (net (code "73") (name "~{DATA8}") (class "Default")
      (node (ref "DR1") (pin "1") (pinfunction "P_1") (pintype "passive"))
      (node (ref "E1") (pin "8") (pinfunction "IO4_8") (pintype "bidirectional"))
    )
    (net (code "74") (name "~{DATA9}") (class "Default")
      (node (ref "DS1") (pin "1") (pinfunction "P_1") (pintype "passive"))
      (node (ref "E1") (pin "3") (pinfunction "IO/PD1_3") (pintype "bidirectional"))
    )
    (net (code "75") (name "~{DATA10}") (class "Default")
      (node (ref "DU1") (pin "1") (pinfunction "P_1") (pintype "passive"))
      (node (ref "E1") (pin "7") (pinfunction "IO3_7") (pintype "bidirectional"))
    )
    (net (code "76") (name "~{DATA11}") (class "Default")
      (node (ref "DV1") (pin "1") (pinfunction "P_1") (pintype "passive"))
      (node (ref "E1") (pin "4") (pinfunction "IO2_4") (pintype "bidirectional"))
    )
    (net (code "77") (name "~{DONE_SKIP}") (class "Default")
      (node (ref "CB1") (pin "1") (pinfunction "P_1") (pintype "passive"))
      (node (ref "E1") (pin "62") (pinfunction "IO48_62") (pintype "bidirectional"))
    )
    (net (code "78") (name "~{INTERNAL_IO}") (class "Default")
      (node (ref "CL1") (pin "1") (pinfunction "P_1") (pintype "passive"))
      (node (ref "E1") (pin "21") (pinfunction "IO14_21") (pintype "bidirectional"))
    )
    (net (code "79") (name "~{INT_RQST}") (class "Default")
      (node (ref "CP1") (pin "1") (pinfunction "P_1") (pintype "passive"))
      (node (ref "E1") (pin "16") (pinfunction "IO11_16") (pintype "bidirectional"))
    )
    (net (code "80") (name "~{IO_PAUSE}") (class "Default")
      (node (ref "CD1") (pin "1") (pinfunction "P_1") (pintype "passive"))
      (node (ref "E1") (pin "26") (pinfunction "IO19_26") (pintype "bidirectional"))
    )
    (net (code "81") (name "~{MD03}") (class "Default")
      (node (ref "E1") (pin "47") (pinfunction "IO35_47") (pintype "bidirectional"))
      (node (ref "SV183") (pin "10") (pinfunction "10_10") (pintype "passive"))
      (node (ref "SV183") (pin "9") (pinfunction "9_9") (pintype "passive"))
    )
    (net (code "82") (name "~{MD04}") (class "Default")
      (node (ref "E1") (pin "38") (pinfunction "IO29_38") (pintype "bidirectional"))
      (node (ref "SV182") (pin "15") (pinfunction "15_15") (pintype "passive"))
      (node (ref "SV182") (pin "16") (pinfunction "16_16") (pintype "passive"))
    )
    (net (code "83") (name "~{MD05}") (class "Default")
      (node (ref "E1") (pin "37") (pinfunction "IO28_37") (pintype "bidirectional"))
      (node (ref "SV182") (pin "13") (pinfunction "13_13") (pintype "passive"))
      (node (ref "SV182") (pin "14") (pinfunction "14_14") (pintype "passive"))
    )
    (net (code "84") (name "~{MD06}") (class "Default")
      (node (ref "E1") (pin "35") (pinfunction "IO27_35") (pintype "bidirectional"))
      (node (ref "E31") (pin "4") (pinfunction "4_4") (pintype "passive"))
      (node (ref "SV182") (pin "11") (pinfunction "11_11") (pintype "passive"))
      (node (ref "SV182") (pin "12") (pinfunction "12_12") (pintype "passive"))
    )
    (net (code "85") (name "~{MD07}") (class "Default")
      (node (ref "E1") (pin "34") (pinfunction "IO26_34") (pintype "bidirectional"))
      (node (ref "E31") (pin "5") (pinfunction "5_5") (pintype "passive"))
      (node (ref "SV182") (pin "10") (pinfunction "10_10") (pintype "passive"))
      (node (ref "SV182") (pin "9") (pinfunction "9_9") (pintype "passive"))
    )
    (net (code "86") (name "~{MD08}") (class "Default")
      (node (ref "DK1") (pin "1") (pinfunction "P_1") (pintype "passive"))
      (node (ref "E1") (pin "12") (pinfunction "IO8_12") (pintype "bidirectional"))
      (node (ref "E31") (pin "6") (pinfunction "6_6") (pintype "passive"))
    )
    (net (code "87") (name "~{MD09}") (class "Default")
      (node (ref "DL1") (pin "1") (pinfunction "P_1") (pintype "passive"))
      (node (ref "E1") (pin "11") (pinfunction "IO7_11") (pintype "bidirectional"))
    )
    (net (code "88") (name "~{MD10}") (class "Default")
      (node (ref "DM1") (pin "1") (pinfunction "P_1") (pintype "passive"))
      (node (ref "E1") (pin "10") (pinfunction "IO6_10") (pintype "bidirectional"))
    )
    (net (code "89") (name "~{MD11}") (class "Default")
      (node (ref "DP1") (pin "1") (pinfunction "P_1") (pintype "passive"))
      (node (ref "E1") (pin "9") (pinfunction "IO5_9") (pintype "bidirectional"))
    )
    (net (code "90") (name "~{RX_12_BIT}") (class "Default")
      (node (ref "DRIVE") (pin "FF") (pinfunction "28_FF") (pintype "bidirectional"))
      (node (ref "IC2") (pin "3") (pinfunction "O_3") (pintype "open_collector"))
      (node (ref "J1") (pin "2") (pinfunction "2_2") (pintype "bidirectional"))
      (node (ref "R16") (pin "2") (pinfunction "2_2") (pintype "passive"))
      (node (ref "R7") (pin "1") (pinfunction "1_1") (pintype "passive"))
    )
    (net (code "91") (name "~{RX_DATA}") (class "Default")
      (node (ref "DRIVE") (pin "BB") (pinfunction "24_BB") (pintype "bidirectional"))
      (node (ref "IC1") (pin "3") (pinfunction "O_3") (pintype "open_collector"))
      (node (ref "J2") (pin "2") (pinfunction "2_2") (pintype "bidirectional"))
      (node (ref "R17") (pin "2") (pinfunction "2_2") (pintype "passive"))
      (node (ref "R8") (pin "1") (pinfunction "1_1") (pintype "passive"))
    )
    (net (code "92") (name "~{RX_DONE}") (class "Default")
      (node (ref "DRIVE") (pin "X") (pinfunction "20_X") (pintype "bidirectional"))
      (node (ref "E1") (pin "81") (pinfunction "IO63_81") (pintype "bidirectional"))
      (node (ref "R13") (pin "2") (pinfunction "2_2") (pintype "passive"))
      (node (ref "R4") (pin "1") (pinfunction "1_1") (pintype "passive"))
    )
    (net (code "93") (name "~{RX_ERROR}") (class "Default")
      (node (ref "DRIVE") (pin "J") (pinfunction "8_J") (pintype "bidirectional"))
      (node (ref "E1") (pin "74") (pinfunction "IO58_74") (pintype "bidirectional"))
      (node (ref "R14") (pin "2") (pinfunction "2_2") (pintype "passive"))
      (node (ref "R5") (pin "1") (pinfunction "1_1") (pintype "passive"))
    )
    (net (code "94") (name "~{RX_INIT}") (class "Default")
      (node (ref "DRIVE") (pin "N") (pinfunction "12_N") (pintype "bidirectional"))
      (node (ref "IC2") (pin "5") (pinfunction "O_5") (pintype "open_collector"))
      (node (ref "J3") (pin "2") (pinfunction "2_2") (pintype "bidirectional"))
      (node (ref "R9") (pin "1") (pinfunction "1_1") (pintype "passive"))
    )
    (net (code "95") (name "~{RX_OUT}") (class "Default")
      (node (ref "DRIVE") (pin "RR") (pinfunction "36_RR") (pintype "bidirectional"))
      (node (ref "E1") (pin "1") (pinfunction "IO75_1") (pintype "bidirectional"))
      (node (ref "R12") (pin "2") (pinfunction "2_2") (pintype "passive"))
      (node (ref "R3") (pin "1") (pinfunction "1_1") (pintype "passive"))
    )
    (net (code "96") (name "~{RX_RUN}") (class "Default")
      (node (ref "DRIVE") (pin "D") (pinfunction "4_D") (pintype "bidirectional"))
      (node (ref "IC1") (pin "5") (pinfunction "O_5") (pintype "open_collector"))
      (node (ref "J4") (pin "2") (pinfunction "2_2") (pintype "bidirectional"))
      (node (ref "R15") (pin "2") (pinfunction "2_2") (pintype "passive"))
      (node (ref "R6") (pin "1") (pinfunction "1_1") (pintype "passive"))
    )
    (net (code "97") (name "~{RX_SHIFT}") (class "Default")
      (node (ref "DRIVE") (pin "LL") (pinfunction "32_LL") (pintype "bidirectional"))
      (node (ref "E1") (pin "99") (pinfunction "IO73_99") (pintype "bidirectional"))
      (node (ref "R10") (pin "2") (pinfunction "2_2") (pintype "passive"))
      (node (ref "R2") (pin "1") (pinfunction "1_1") (pintype "passive"))
    )
    (net (code "98") (name "~{RX_TR_REQ}") (class "Default")
      (node (ref "DRIVE") (pin "T") (pinfunction "16_T") (pintype "bidirectional"))
      (node (ref "E1") (pin "79") (pinfunction "IO61_79") (pintype "bidirectional"))
      (node (ref "R1") (pin "1") (pinfunction "1_1") (pintype "passive"))
      (node (ref "R11") (pin "2") (pinfunction "2_2") (pintype "passive"))
    )
    (net (code "99") (name "~{SKIP}") (class "Default")
      (node (ref "CS1") (pin "1") (pinfunction "P_1") (pintype "passive"))
      (node (ref "E1") (pin "14") (pinfunction "IO9_14") (pintype "bidirectional"))
    )
    (net (code "100") (name "~{TR_SKIP}") (class "Default")
      (node (ref "DB1") (pin "1") (pinfunction "P_1") (pintype "passive"))
      (node (ref "E1") (pin "63") (pinfunction "IO49_63") (pintype "bidirectional"))
    )
  )
)
